# connect.net
KiCad netlist of a schematic drawn in Altium Designer
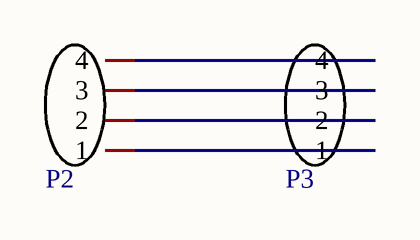
[diagram p0: connect.SchDoc]

(export (version "E")
  (design (tool "Eeschema 10.0.6"))
  (components
    (comp (ref "P2")
      (value "HDR1x4_1.27")
      (footprint "ServoDrive:FPC-SMD_4P-P0.50_DEALON_0.5K-DX-4PWB")
      (description "Header")
      (libsource (lib "altium-import") (part "root_2_HDR1x4_1.27_"))
    )
    (comp (ref "P3")
      (value "HDR1x4_1.27")
      (footprint "ServoDrive:HDR1X4_1.27_180")
      (description "Header")
      (libsource (lib "altium-import") (part "root_2_HDR1x4_1.27_"))
    )
  )
  (nets
    (net (code "1") (name "Net-(P2-Pad1)") (class "Default")
      (node (ref "P2") (pin "1") (pinfunction "1_1") (pintype "passive"))
      (node (ref "P3") (pin "1") (pinfunction "1_1") (pintype "passive"))
    )
    (net (code "2") (name "Net-(P2-Pad2)") (class "Default")
      (node (ref "P2") (pin "2") (pinfunction "2_2") (pintype "passive"))
      (node (ref "P3") (pin "2") (pinfunction "2_2") (pintype "passive"))
    )
    (net (code "3") (name "Net-(P2-Pad3)") (class "Default")
      (node (ref "P2") (pin "3") (pinfunction "3_3") (pintype "passive"))
      (node (ref "P3") (pin "3") (pinfunction "3_3") (pintype "passive"))
    )
    (net (code "4") (name "Net-(P2-Pad4)") (class "Default")
      (node (ref "P2") (pin "4") (pinfunction "4_4") (pintype "passive"))
      (node (ref "P3") (pin "4") (pinfunction "4_4") (pintype "passive"))
    )
  )
)
